# Battery_PCB_8x4.net
KiCad netlist of a schematic drawn in Altium Designer
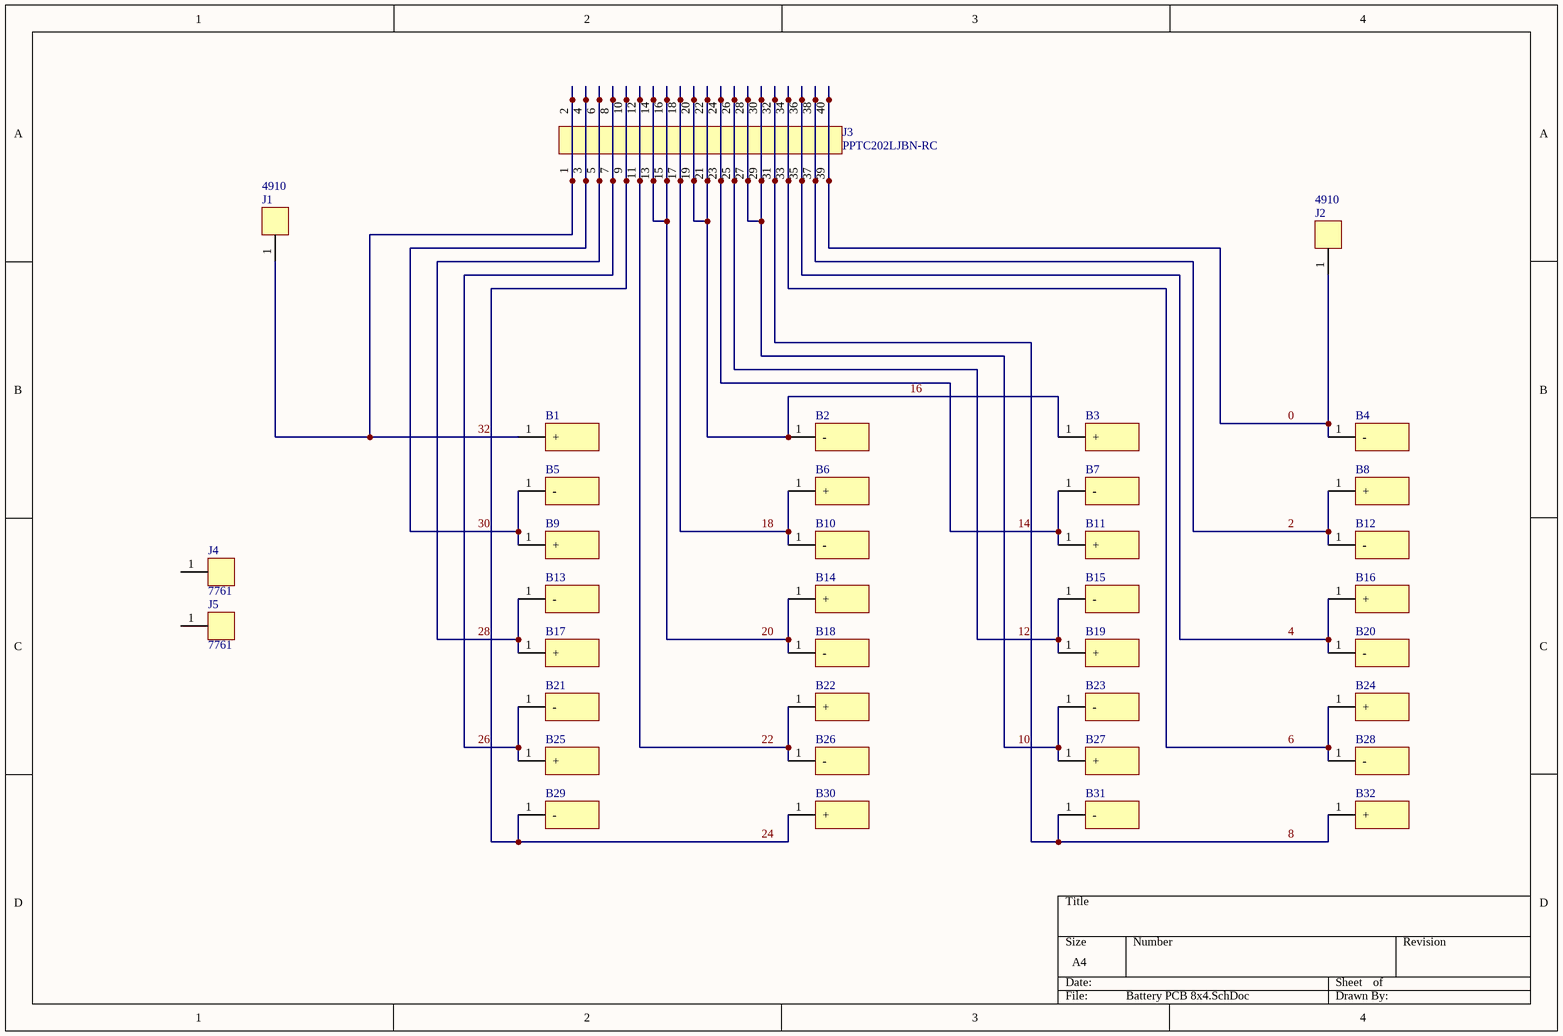
[diagram p0: Battery PCB 8x4.SchDoc]

(export (version "E")
  (design (tool "Eeschema 10.0.6"))
  (components
    (comp (ref "B1")
      (value "Positive side of battery")
      (footprint "BF_BATT_P")
      (libsource (lib "Bad-Fox") (part "BF_BATT_P"))
    )
    (comp (ref "B2")
      (value "Negative side of battery")
      (footprint "BF_BATT_N")
      (libsource (lib "Bad-Fox") (part "BF_BATT_N"))
    )
    (comp (ref "B3")
      (value "Positive side of battery")
      (footprint "BF_BATT_P")
      (libsource (lib "Bad-Fox") (part "BF_BATT_P"))
    )
    (comp (ref "B4")
      (value "Negative side of battery")
      (footprint "BF_BATT_N")
      (libsource (lib "Bad-Fox") (part "BF_BATT_N"))
    )
    (comp (ref "B5")
      (value "Negative side of battery")
      (footprint "BF_BATT_N")
      (libsource (lib "Bad-Fox") (part "BF_BATT_N"))
    )
    (comp (ref "B6")
      (value "Positive side of battery")
      (footprint "BF_BATT_P")
      (libsource (lib "Bad-Fox") (part "BF_BATT_P"))
    )
    (comp (ref "B7")
      (value "Negative side of battery")
      (footprint "BF_BATT_N")
      (libsource (lib "Bad-Fox") (part "BF_BATT_N"))
    )
    (comp (ref "B8")
      (value "Positive side of battery")
      (footprint "BF_BATT_P")
      (libsource (lib "Bad-Fox") (part "BF_BATT_P"))
    )
    (comp (ref "B9")
      (value "Positive side of battery")
      (footprint "BF_BATT_P")
      (libsource (lib "Bad-Fox") (part "BF_BATT_P"))
    )
    (comp (ref "B10")
      (value "Negative side of battery")
      (footprint "BF_BATT_N")
      (libsource (lib "Bad-Fox") (part "BF_BATT_N"))
    )
    (comp (ref "B11")
      (value "Positive side of battery")
      (footprint "BF_BATT_P")
      (libsource (lib "Bad-Fox") (part "BF_BATT_P"))
    )
    (comp (ref "B12")
      (value "Negative side of battery")
      (footprint "BF_BATT_N")
      (libsource (lib "Bad-Fox") (part "BF_BATT_N"))
    )
    (comp (ref "B13")
      (value "Negative side of battery")
      (footprint "BF_BATT_N")
      (libsource (lib "Bad-Fox") (part "BF_BATT_N"))
    )
    (comp (ref "B14")
      (value "Positive side of battery")
      (footprint "BF_BATT_P")
      (libsource (lib "Bad-Fox") (part "BF_BATT_P"))
    )
    (comp (ref "B15")
      (value "Negative side of battery")
      (footprint "BF_BATT_N")
      (libsource (lib "Bad-Fox") (part "BF_BATT_N"))
    )
    (comp (ref "B16")
      (value "Positive side of battery")
      (footprint "BF_BATT_P")
      (libsource (lib "Bad-Fox") (part "BF_BATT_P"))
    )
    (comp (ref "B17")
      (value "Positive side of battery")
      (footprint "BF_BATT_P")
      (libsource (lib "Bad-Fox") (part "BF_BATT_P"))
    )
    (comp (ref "B18")
      (value "Negative side of battery")
      (footprint "BF_BATT_N")
      (libsource (lib "Bad-Fox") (part "BF_BATT_N"))
    )
    (comp (ref "B19")
      (value "Positive side of battery")
      (footprint "BF_BATT_P")
      (libsource (lib "Bad-Fox") (part "BF_BATT_P"))
    )
    (comp (ref "B20")
      (value "Negative side of battery")
      (footprint "BF_BATT_N")
      (libsource (lib "Bad-Fox") (part "BF_BATT_N"))
    )
    (comp (ref "B21")
      (value "Negative side of battery")
      (footprint "BF_BATT_N")
      (libsource (lib "Bad-Fox") (part "BF_BATT_N"))
    )
    (comp (ref "B22")
      (value "Positive side of battery")
      (footprint "BF_BATT_P")
      (libsource (lib "Bad-Fox") (part "BF_BATT_P"))
    )
    (comp (ref "B23")
      (value "Negative side of battery")
      (footprint "BF_BATT_N")
      (libsource (lib "Bad-Fox") (part "BF_BATT_N"))
    )
    (comp (ref "B24")
      (value "Positive side of battery")
      (footprint "BF_BATT_P")
      (libsource (lib "Bad-Fox") (part "BF_BATT_P"))
    )
    (comp (ref "B25")
      (value "Positive side of battery")
      (footprint "BF_BATT_P")
      (libsource (lib "Bad-Fox") (part "BF_BATT_P"))
    )
    (comp (ref "B26")
      (value "Negative side of battery")
      (footprint "BF_BATT_N")
      (libsource (lib "Bad-Fox") (part "BF_BATT_N"))
    )
    (comp (ref "B27")
      (value "Positive side of battery")
      (footprint "BF_BATT_P")
      (libsource (lib "Bad-Fox") (part "BF_BATT_P"))
    )
    (comp (ref "B28")
      (value "Negative side of battery")
      (footprint "BF_BATT_N")
      (libsource (lib "Bad-Fox") (part "BF_BATT_N"))
    )
    (comp (ref "B29")
      (value "Negative side of battery")
      (footprint "BF_BATT_N")
      (libsource (lib "Bad-Fox") (part "BF_BATT_N"))
    )
    (comp (ref "B30")
      (value "Positive side of battery")
      (footprint "BF_BATT_P")
      (libsource (lib "Bad-Fox") (part "BF_BATT_P"))
    )
    (comp (ref "B31")
      (value "Negative side of battery")
      (footprint "BF_BATT_N")
      (libsource (lib "Bad-Fox") (part "BF_BATT_N"))
    )
    (comp (ref "B32")
      (value "Positive side of battery")
      (footprint "BF_BATT_P")
      (libsource (lib "Bad-Fox") (part "BF_BATT_P"))
    )
    (comp (ref "J1")
      (value "4910")
      (footprint "4910")
      (description "Conn QC TAB 0.250 RA TH")
      (fields (field (name "MFG") "Keystone Electronics"))
      (libsource (lib "Bad-Fox") (part "4910"))
    )
    (comp (ref "J2")
      (value "4910")
      (footprint "4910")
      (description "Conn QC TAB 0.250 RA TH")
      (fields (field (name "MFG") "Keystone Electronics"))
      (libsource (lib "Bad-Fox") (part "4910"))
    )
    (comp (ref "J3")
      (value "PPTC202LJBN-RC")
      (footprint "PPTC202LJBN-RC")
      (description "Conn Recept 40Pos 0.1\" dual row TH RA")
      (fields (field (name "MFG") "Sullins Connector Solutions"))
      (libsource (lib "Bad-Fox") (part "PPTC202LJBN-RC"))
    )
    (comp (ref "J4")
      (value "7761")
      (footprint "7761")
      (description "Conn Screw M3 RA TH")
      (fields (field (name "MFG") "Keystone Electronics"))
      (libsource (lib "Bad-Fox") (part "7761"))
    )
    (comp (ref "J5")
      (value "7761")
      (footprint "7761")
      (description "Conn Screw M3 RA TH")
      (fields (field (name "MFG") "Keystone Electronics"))
      (libsource (lib "Bad-Fox") (part "7761"))
    )
  )
  (nets
    (net (code "1") (name "/0") (class "Default")
      (node (ref "B4") (pin "1") (pinfunction "-_1") (pintype "passive"))
      (node (ref "J2") (pin "1") (pintype "passive"))
      (node (ref "J3") (pin "39") (pintype "passive"))
      (node (ref "J3") (pin "40") (pintype "passive"))
    )
    (net (code "2") (name "/2") (class "Default")
      (node (ref "B12") (pin "1") (pinfunction "-_1") (pintype "passive"))
      (node (ref "B8") (pin "1") (pinfunction "+_1") (pintype "passive"))
      (node (ref "J3") (pin "37") (pintype "passive"))
      (node (ref "J3") (pin "38") (pintype "passive"))
    )
    (net (code "3") (name "/4") (class "Default")
      (node (ref "B16") (pin "1") (pinfunction "+_1") (pintype "passive"))
      (node (ref "B20") (pin "1") (pinfunction "-_1") (pintype "passive"))
      (node (ref "J3") (pin "35") (pintype "passive"))
      (node (ref "J3") (pin "36") (pintype "passive"))
    )
    (net (code "4") (name "/6") (class "Default")
      (node (ref "B24") (pin "1") (pinfunction "+_1") (pintype "passive"))
      (node (ref "B28") (pin "1") (pinfunction "-_1") (pintype "passive"))
      (node (ref "J3") (pin "33") (pintype "passive"))
      (node (ref "J3") (pin "34") (pintype "passive"))
    )
    (net (code "5") (name "/8") (class "Default")
      (node (ref "B31") (pin "1") (pinfunction "-_1") (pintype "passive"))
      (node (ref "B32") (pin "1") (pinfunction "+_1") (pintype "passive"))
      (node (ref "J3") (pin "31") (pintype "passive"))
      (node (ref "J3") (pin "32") (pintype "passive"))
    )
    (net (code "6") (name "/10") (class "Default")
      (node (ref "B23") (pin "1") (pinfunction "-_1") (pintype "passive"))
      (node (ref "B27") (pin "1") (pinfunction "+_1") (pintype "passive"))
      (node (ref "J3") (pin "27") (pintype "passive"))
      (node (ref "J3") (pin "28") (pintype "passive"))
      (node (ref "J3") (pin "29") (pintype "passive"))
      (node (ref "J3") (pin "30") (pintype "passive"))
    )
    (net (code "7") (name "/12") (class "Default")
      (node (ref "B15") (pin "1") (pinfunction "-_1") (pintype "passive"))
      (node (ref "B19") (pin "1") (pinfunction "+_1") (pintype "passive"))
      (node (ref "J3") (pin "25") (pintype "passive"))
      (node (ref "J3") (pin "26") (pintype "passive"))
    )
    (net (code "8") (name "/14") (class "Default")
      (node (ref "B11") (pin "1") (pinfunction "+_1") (pintype "passive"))
      (node (ref "B7") (pin "1") (pinfunction "-_1") (pintype "passive"))
      (node (ref "J3") (pin "23") (pintype "passive"))
      (node (ref "J3") (pin "24") (pintype "passive"))
    )
    (net (code "9") (name "/16") (class "Default")
      (node (ref "B2") (pin "1") (pinfunction "-_1") (pintype "passive"))
      (node (ref "B3") (pin "1") (pinfunction "+_1") (pintype "passive"))
      (node (ref "J3") (pin "19") (pintype "passive"))
      (node (ref "J3") (pin "20") (pintype "passive"))
      (node (ref "J3") (pin "21") (pintype "passive"))
      (node (ref "J3") (pin "22") (pintype "passive"))
    )
    (net (code "10") (name "/18") (class "Default")
      (node (ref "B10") (pin "1") (pinfunction "-_1") (pintype "passive"))
      (node (ref "B6") (pin "1") (pinfunction "+_1") (pintype "passive"))
      (node (ref "J3") (pin "17") (pintype "passive"))
      (node (ref "J3") (pin "18") (pintype "passive"))
    )
    (net (code "11") (name "/20") (class "Default")
      (node (ref "B14") (pin "1") (pinfunction "+_1") (pintype "passive"))
      (node (ref "B18") (pin "1") (pinfunction "-_1") (pintype "passive"))
      (node (ref "J3") (pin "13") (pintype "passive"))
      (node (ref "J3") (pin "14") (pintype "passive"))
      (node (ref "J3") (pin "15") (pintype "passive"))
      (node (ref "J3") (pin "16") (pintype "passive"))
    )
    (net (code "12") (name "/22") (class "Default")
      (node (ref "B22") (pin "1") (pinfunction "+_1") (pintype "passive"))
      (node (ref "B26") (pin "1") (pinfunction "-_1") (pintype "passive"))
      (node (ref "J3") (pin "11") (pintype "passive"))
      (node (ref "J3") (pin "12") (pintype "passive"))
    )
    (net (code "13") (name "/24") (class "Default")
      (node (ref "B29") (pin "1") (pinfunction "-_1") (pintype "passive"))
      (node (ref "B30") (pin "1") (pinfunction "+_1") (pintype "passive"))
      (node (ref "J3") (pin "10") (pintype "passive"))
      (node (ref "J3") (pin "9") (pintype "passive"))
    )
    (net (code "14") (name "/26") (class "Default")
      (node (ref "B21") (pin "1") (pinfunction "-_1") (pintype "passive"))
      (node (ref "B25") (pin "1") (pinfunction "+_1") (pintype "passive"))
      (node (ref "J3") (pin "7") (pintype "passive"))
      (node (ref "J3") (pin "8") (pintype "passive"))
    )
    (net (code "15") (name "/28") (class "Default")
      (node (ref "B13") (pin "1") (pinfunction "-_1") (pintype "passive"))
      (node (ref "B17") (pin "1") (pinfunction "+_1") (pintype "passive"))
      (node (ref "J3") (pin "5") (pintype "passive"))
      (node (ref "J3") (pin "6") (pintype "passive"))
    )
    (net (code "16") (name "/30") (class "Default")
      (node (ref "B5") (pin "1") (pinfunction "-_1") (pintype "passive"))
      (node (ref "B9") (pin "1") (pinfunction "+_1") (pintype "passive"))
      (node (ref "J3") (pin "3") (pintype "passive"))
      (node (ref "J3") (pin "4") (pintype "passive"))
    )
    (net (code "17") (name "/32") (class "Default")
      (node (ref "B1") (pin "1") (pinfunction "+_1") (pintype "passive"))
      (node (ref "J1") (pin "1") (pintype "passive"))
      (node (ref "J3") (pin "1") (pintype "passive"))
      (node (ref "J3") (pin "2") (pintype "passive"))
    )
    (net (code "18") (name "unconnected-(J4-Pad1)") (class "Default")
      (node (ref "J4") (pin "1") (pintype "passive"))
    )
    (net (code "19") (name "unconnected-(J5-Pad1)") (class "Default")
      (node (ref "J5") (pin "1") (pintype "passive"))
    )
  )
)
